# dynalov3.net
KiCad netlist of a schematic drawn in EAGLE
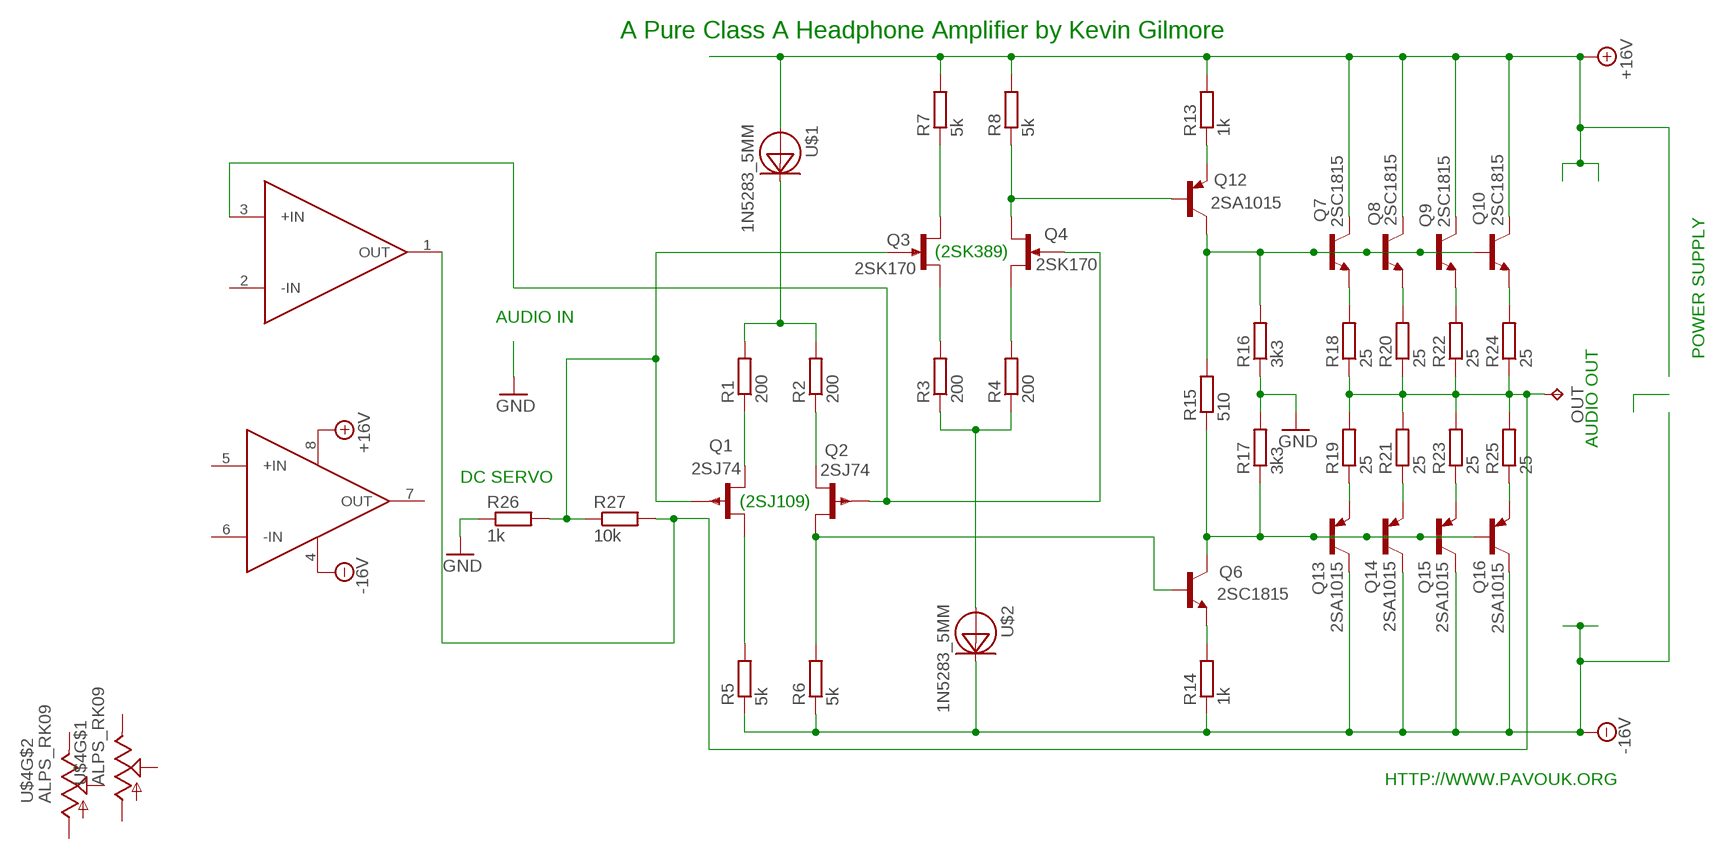
[diagram p0: schematic, sheet 1]

(export (version "E")
  (design (tool "Eeschema 10.0.6"))
  (components
    (comp (ref "OUT")
      (value "TPPAD1-20")
      (footprint "eagle-import:P1-20")
      (libsource (lib "eagle-import") (part "TPPAD1-20"))
    )
    (comp (ref "Q1")
      (value "2SJ74")
      (footprint "eagle-import:TO92F")
      (libsource (lib "eagle-import") (part "2N3820"))
    )
    (comp (ref "Q2")
      (value "2SJ74")
      (footprint "eagle-import:TO92F")
      (libsource (lib "eagle-import") (part "2N3820"))
    )
    (comp (ref "Q3")
      (value "2SK170")
      (footprint "eagle-import:TO92F")
      (libsource (lib "eagle-import") (part "2N3819"))
    )
    (comp (ref "Q4")
      (value "2SK170")
      (footprint "eagle-import:TO92F")
      (libsource (lib "eagle-import") (part "2N3819"))
    )
    (comp (ref "Q6")
      (value "2SC1815")
      (footprint "eagle-import:TO92-ECB")
      (libsource (lib "eagle-import") (part "2SC1815"))
    )
    (comp (ref "Q7")
      (value "2SC1815")
      (footprint "eagle-import:TO92-ECB")
      (libsource (lib "eagle-import") (part "2SC1815"))
    )
    (comp (ref "Q8")
      (value "2SC1815")
      (footprint "eagle-import:TO92-ECB")
      (libsource (lib "eagle-import") (part "2SC1815"))
    )
    (comp (ref "Q9")
      (value "2SC1815")
      (footprint "eagle-import:TO92-ECB")
      (libsource (lib "eagle-import") (part "2SC1815"))
    )
    (comp (ref "Q10")
      (value "2SC1815")
      (footprint "eagle-import:TO92-ECB")
      (libsource (lib "eagle-import") (part "2SC1815"))
    )
    (comp (ref "Q12")
      (value "2SA1015")
      (footprint "eagle-import:TO92-ECB")
      (libsource (lib "eagle-import") (part "-PNP-TO92-ECB"))
    )
    (comp (ref "Q13")
      (value "2SA1015")
      (footprint "eagle-import:TO92-ECB")
      (libsource (lib "eagle-import") (part "-PNP-TO92-ECB"))
    )
    (comp (ref "Q14")
      (value "2SA1015")
      (footprint "eagle-import:TO92-ECB")
      (libsource (lib "eagle-import") (part "-PNP-TO92-ECB"))
    )
    (comp (ref "Q15")
      (value "2SA1015")
      (footprint "eagle-import:TO92-ECB")
      (libsource (lib "eagle-import") (part "-PNP-TO92-ECB"))
    )
    (comp (ref "Q16")
      (value "2SA1015")
      (footprint "eagle-import:TO92-ECB")
      (libsource (lib "eagle-import") (part "-PNP-TO92-ECB"))
    )
    (comp (ref "R1")
      (value "200")
      (footprint "eagle-import:MINI_MELF-0204W")
      (libsource (lib "eagle-import") (part "R-EU_MELF0204W"))
    )
    (comp (ref "R2")
      (value "200")
      (footprint "eagle-import:MINI_MELF-0204W")
      (libsource (lib "eagle-import") (part "R-EU_MELF0204W"))
    )
    (comp (ref "R3")
      (value "200")
      (footprint "eagle-import:MINI_MELF-0204W")
      (libsource (lib "eagle-import") (part "R-EU_MELF0204W"))
    )
    (comp (ref "R4")
      (value "200")
      (footprint "eagle-import:MINI_MELF-0204W")
      (libsource (lib "eagle-import") (part "R-EU_MELF0204W"))
    )
    (comp (ref "R5")
      (value "5k")
      (footprint "eagle-import:MINI_MELF-0204W")
      (libsource (lib "eagle-import") (part "R-EU_MELF0204W"))
    )
    (comp (ref "R6")
      (value "5k")
      (footprint "eagle-import:MINI_MELF-0204W")
      (libsource (lib "eagle-import") (part "R-EU_MELF0204W"))
    )
    (comp (ref "R7")
      (value "5k")
      (footprint "eagle-import:MINI_MELF-0204W")
      (libsource (lib "eagle-import") (part "R-EU_MELF0204W"))
    )
    (comp (ref "R8")
      (value "5k")
      (footprint "eagle-import:MINI_MELF-0204W")
      (libsource (lib "eagle-import") (part "R-EU_MELF0204W"))
    )
    (comp (ref "R13")
      (value "1k")
      (footprint "eagle-import:MINI_MELF-0204W")
      (libsource (lib "eagle-import") (part "R-EU_MELF0204W"))
    )
    (comp (ref "R14")
      (value "1k")
      (footprint "eagle-import:MINI_MELF-0204W")
      (libsource (lib "eagle-import") (part "R-EU_MELF0204W"))
    )
    (comp (ref "R15")
      (value "510")
      (footprint "eagle-import:MINI_MELF-0204W")
      (libsource (lib "eagle-import") (part "R-EU_MELF0204W"))
    )
    (comp (ref "R16")
      (value "3k3")
      (footprint "eagle-import:MINI_MELF-0204W")
      (libsource (lib "eagle-import") (part "R-EU_MELF0204W"))
    )
    (comp (ref "R17")
      (value "3k3")
      (footprint "eagle-import:MINI_MELF-0204W")
      (libsource (lib "eagle-import") (part "R-EU_MELF0204W"))
    )
    (comp (ref "R18")
      (value "25")
      (footprint "eagle-import:MINI_MELF-0204W")
      (libsource (lib "eagle-import") (part "R-EU_MELF0204W"))
    )
    (comp (ref "R19")
      (value "25")
      (footprint "eagle-import:MINI_MELF-0204W")
      (libsource (lib "eagle-import") (part "R-EU_MELF0204W"))
    )
    (comp (ref "R20")
      (value "25")
      (footprint "eagle-import:MINI_MELF-0204W")
      (libsource (lib "eagle-import") (part "R-EU_MELF0204W"))
    )
    (comp (ref "R21")
      (value "25")
      (footprint "eagle-import:MINI_MELF-0204W")
      (libsource (lib "eagle-import") (part "R-EU_MELF0204W"))
    )
    (comp (ref "R22")
      (value "25")
      (footprint "eagle-import:MINI_MELF-0204W")
      (libsource (lib "eagle-import") (part "R-EU_MELF0204W"))
    )
    (comp (ref "R23")
      (value "25")
      (footprint "eagle-import:MINI_MELF-0204W")
      (libsource (lib "eagle-import") (part "R-EU_MELF0204W"))
    )
    (comp (ref "R24")
      (value "25")
      (footprint "eagle-import:MINI_MELF-0204W")
      (libsource (lib "eagle-import") (part "R-EU_MELF0204W"))
    )
    (comp (ref "R25")
      (value "25")
      (footprint "eagle-import:MINI_MELF-0204W")
      (libsource (lib "eagle-import") (part "R-EU_MELF0204W"))
    )
    (comp (ref "R26")
      (value "1k")
      (footprint "eagle-import:MINI_MELF-0204W")
      (libsource (lib "eagle-import") (part "R-EU_MELF0204W"))
    )
    (comp (ref "R27")
      (value "10k")
      (footprint "eagle-import:MINI_MELF-0204W")
      (libsource (lib "eagle-import") (part "R-EU_MELF0204W"))
    )
    (comp (ref "U$1")
      (value "1N5283_5MM")
      (footprint "eagle-import:DO-35-2")
      (libsource (lib "eagle-import") (part "1N5283_5MM"))
    )
    (comp (ref "U$2")
      (value "1N5283_5MM")
      (footprint "eagle-import:DO-35-2")
      (libsource (lib "eagle-import") (part "1N5283_5MM"))
    )
    (comp (ref "U$3")
      (value "LME49720")
      (footprint "eagle-import:DIL08")
      (libsource (lib "eagle-import") (part "LME49720"))
    )
    (comp (ref "U$4")
      (value "ALPS_RK09")
      (footprint "eagle-import:RK09")
      (libsource (lib "eagle-import") (part "ALPS_RK09"))
    )
  )
  (nets
    (net (code "1") (name "+16V") (class "Default")
      (node (ref "Q10") (pin "C") (pinfunction "C_C") (pintype "passive"))
      (node (ref "Q7") (pin "C") (pinfunction "C_C") (pintype "passive"))
      (node (ref "Q8") (pin "C") (pinfunction "C_C") (pintype "passive"))
      (node (ref "Q9") (pin "C") (pinfunction "C_C") (pintype "passive"))
      (node (ref "R13") (pin "2") (pinfunction "2_2") (pintype "passive"))
      (node (ref "R7") (pin "2") (pinfunction "2_2") (pintype "passive"))
      (node (ref "R8") (pin "2") (pinfunction "2_2") (pintype "passive"))
      (node (ref "U$1") (pin "ANODE") (pinfunction "ANODE_ANODE") (pintype "passive"))
      (node (ref "U$3") (pin "8") (pinfunction "V+_8") (pintype "bidirectional"))
    )
    (net (code "2") (name "-16V") (class "Default")
      (node (ref "Q13") (pin "C") (pinfunction "C_C") (pintype "passive"))
      (node (ref "Q14") (pin "C") (pinfunction "C_C") (pintype "passive"))
      (node (ref "Q15") (pin "C") (pinfunction "C_C") (pintype "passive"))
      (node (ref "Q16") (pin "C") (pinfunction "C_C") (pintype "passive"))
      (node (ref "R14") (pin "1") (pinfunction "1_1") (pintype "passive"))
      (node (ref "R5") (pin "1") (pinfunction "1_1") (pintype "passive"))
      (node (ref "R6") (pin "1") (pinfunction "1_1") (pintype "passive"))
      (node (ref "U$2") (pin "CATHODE") (pinfunction "CATHODE_CATHODE") (pintype "passive"))
      (node (ref "U$3") (pin "4") (pinfunction "V-_4") (pintype "bidirectional"))
    )
    (net (code "3") (name "GND") (class "Default")
      (node (ref "R16") (pin "1") (pinfunction "1_1") (pintype "passive"))
      (node (ref "R17") (pin "2") (pinfunction "2_2") (pintype "passive"))
      (node (ref "R26") (pin "1") (pinfunction "1_1") (pintype "passive"))
    )
    (net (code "4") (name "Net-(Q1-PadD)") (class "Default")
      (node (ref "Q1") (pin "D") (pinfunction "D_D") (pintype "passive"))
      (node (ref "R1") (pin "1") (pinfunction "1_1") (pintype "passive"))
    )
    (net (code "5") (name "Net-(Q1-PadG)") (class "Default")
      (node (ref "Q1") (pin "G") (pinfunction "G_G") (pintype "passive"))
      (node (ref "Q3") (pin "G") (pinfunction "G_G") (pintype "passive"))
      (node (ref "R26") (pin "2") (pinfunction "2_2") (pintype "passive"))
      (node (ref "R27") (pin "1") (pinfunction "1_1") (pintype "passive"))
    )
    (net (code "6") (name "Net-(Q1-PadS)") (class "Default")
      (node (ref "Q1") (pin "S") (pinfunction "S_S") (pintype "passive"))
      (node (ref "R5") (pin "2") (pinfunction "2_2") (pintype "passive"))
    )
    (net (code "7") (name "Net-(Q2-PadD)") (class "Default")
      (node (ref "Q2") (pin "D") (pinfunction "D_D") (pintype "passive"))
      (node (ref "Q6") (pin "B") (pinfunction "B_B") (pintype "passive"))
      (node (ref "R6") (pin "2") (pinfunction "2_2") (pintype "passive"))
    )
    (net (code "8") (name "Net-(Q2-PadS)") (class "Default")
      (node (ref "Q2") (pin "S") (pinfunction "S_S") (pintype "passive"))
      (node (ref "R2") (pin "1") (pinfunction "1_1") (pintype "passive"))
    )
    (net (code "9") (name "Net-(Q3-PadD)") (class "Default")
      (node (ref "Q3") (pin "D") (pinfunction "D_D") (pintype "passive"))
      (node (ref "R7") (pin "1") (pinfunction "1_1") (pintype "passive"))
    )
    (net (code "10") (name "Net-(Q3-PadS)") (class "Default")
      (node (ref "Q3") (pin "S") (pinfunction "S_S") (pintype "passive"))
      (node (ref "R3") (pin "2") (pinfunction "2_2") (pintype "passive"))
    )
    (net (code "11") (name "Net-(Q4-PadD)") (class "Default")
      (node (ref "Q4") (pin "D") (pinfunction "D_D") (pintype "passive"))
      (node (ref "R4") (pin "2") (pinfunction "2_2") (pintype "passive"))
    )
    (net (code "12") (name "Net-(Q6-PadE)") (class "Default")
      (node (ref "Q6") (pin "E") (pinfunction "E_E") (pintype "passive"))
      (node (ref "R14") (pin "2") (pinfunction "2_2") (pintype "passive"))
    )
    (net (code "13") (name "Net-(Q7-PadE)") (class "Default")
      (node (ref "Q7") (pin "E") (pinfunction "E_E") (pintype "passive"))
      (node (ref "R18") (pin "2") (pinfunction "2_2") (pintype "passive"))
    )
    (net (code "14") (name "Net-(Q8-PadE)") (class "Default")
      (node (ref "Q8") (pin "E") (pinfunction "E_E") (pintype "passive"))
      (node (ref "R20") (pin "2") (pinfunction "2_2") (pintype "passive"))
    )
    (net (code "15") (name "Net-(Q9-PadE)") (class "Default")
      (node (ref "Q9") (pin "E") (pinfunction "E_E") (pintype "passive"))
      (node (ref "R22") (pin "2") (pinfunction "2_2") (pintype "passive"))
    )
    (net (code "16") (name "Net-(Q10-PadB)") (class "Default")
      (node (ref "Q10") (pin "B") (pinfunction "B_B") (pintype "passive"))
      (node (ref "Q12") (pin "C") (pinfunction "C_C") (pintype "passive"))
      (node (ref "Q7") (pin "B") (pinfunction "B_B") (pintype "passive"))
      (node (ref "Q8") (pin "B") (pinfunction "B_B") (pintype "passive"))
      (node (ref "Q9") (pin "B") (pinfunction "B_B") (pintype "passive"))
      (node (ref "R15") (pin "2") (pinfunction "2_2") (pintype "passive"))
      (node (ref "R16") (pin "2") (pinfunction "2_2") (pintype "passive"))
    )
    (net (code "17") (name "Net-(Q10-PadE)") (class "Default")
      (node (ref "Q10") (pin "E") (pinfunction "E_E") (pintype "passive"))
      (node (ref "R24") (pin "2") (pinfunction "2_2") (pintype "passive"))
    )
    (net (code "18") (name "Net-(Q12-PadB)") (class "Default")
      (node (ref "Q12") (pin "B") (pinfunction "B_B") (pintype "passive"))
      (node (ref "Q4") (pin "S") (pinfunction "S_S") (pintype "passive"))
      (node (ref "R8") (pin "1") (pinfunction "1_1") (pintype "passive"))
    )
    (net (code "19") (name "Net-(Q12-PadE)") (class "Default")
      (node (ref "Q12") (pin "E") (pinfunction "E_E") (pintype "passive"))
      (node (ref "R13") (pin "1") (pinfunction "1_1") (pintype "passive"))
    )
    (net (code "20") (name "Net-(Q13-PadB)") (class "Default")
      (node (ref "Q13") (pin "B") (pinfunction "B_B") (pintype "passive"))
      (node (ref "Q14") (pin "B") (pinfunction "B_B") (pintype "passive"))
      (node (ref "Q15") (pin "B") (pinfunction "B_B") (pintype "passive"))
      (node (ref "Q16") (pin "B") (pinfunction "B_B") (pintype "passive"))
      (node (ref "Q6") (pin "C") (pinfunction "C_C") (pintype "passive"))
      (node (ref "R15") (pin "1") (pinfunction "1_1") (pintype "passive"))
      (node (ref "R17") (pin "1") (pinfunction "1_1") (pintype "passive"))
    )
    (net (code "21") (name "Net-(Q13-PadE)") (class "Default")
      (node (ref "Q13") (pin "E") (pinfunction "E_E") (pintype "passive"))
      (node (ref "R19") (pin "1") (pinfunction "1_1") (pintype "passive"))
    )
    (net (code "22") (name "Net-(Q14-PadE)") (class "Default")
      (node (ref "Q14") (pin "E") (pinfunction "E_E") (pintype "passive"))
      (node (ref "R21") (pin "1") (pinfunction "1_1") (pintype "passive"))
    )
    (net (code "23") (name "Net-(Q15-PadE)") (class "Default")
      (node (ref "Q15") (pin "E") (pinfunction "E_E") (pintype "passive"))
      (node (ref "R23") (pin "1") (pinfunction "1_1") (pintype "passive"))
    )
    (net (code "24") (name "Net-(Q16-PadE)") (class "Default")
      (node (ref "Q16") (pin "E") (pinfunction "E_E") (pintype "passive"))
      (node (ref "R25") (pin "1") (pinfunction "1_1") (pintype "passive"))
    )
    (net (code "25") (name "Net-(R1-Pad2)") (class "Default")
      (node (ref "R1") (pin "2") (pinfunction "2_2") (pintype "passive"))
      (node (ref "R2") (pin "2") (pinfunction "2_2") (pintype "passive"))
      (node (ref "U$1") (pin "CATHODE") (pinfunction "CATHODE_CATHODE") (pintype "passive"))
    )
    (net (code "26") (name "Net-(R3-Pad1)") (class "Default")
      (node (ref "R3") (pin "1") (pinfunction "1_1") (pintype "passive"))
      (node (ref "R4") (pin "1") (pinfunction "1_1") (pintype "passive"))
      (node (ref "U$2") (pin "ANODE") (pinfunction "ANODE_ANODE") (pintype "passive"))
    )
    (net (code "27") (name "Net-(U$3A-+IN)") (class "Default")
      (node (ref "Q2") (pin "G") (pinfunction "G_G") (pintype "passive"))
      (node (ref "Q4") (pin "G") (pinfunction "G_G") (pintype "passive"))
      (node (ref "U$3") (pin "3") (pinfunction "+IN_3") (pintype "bidirectional"))
    )
    (net (code "28") (name "Net-(U$3A-OUT)") (class "Default")
      (node (ref "OUT") (pin "TP") (pinfunction "TP_TP") (pintype "input"))
      (node (ref "R18") (pin "1") (pinfunction "1_1") (pintype "passive"))
      (node (ref "R19") (pin "2") (pinfunction "2_2") (pintype "passive"))
      (node (ref "R20") (pin "1") (pinfunction "1_1") (pintype "passive"))
      (node (ref "R21") (pin "2") (pinfunction "2_2") (pintype "passive"))
      (node (ref "R22") (pin "1") (pinfunction "1_1") (pintype "passive"))
      (node (ref "R23") (pin "2") (pinfunction "2_2") (pintype "passive"))
      (node (ref "R24") (pin "1") (pinfunction "1_1") (pintype "passive"))
      (node (ref "R25") (pin "2") (pinfunction "2_2") (pintype "passive"))
      (node (ref "R27") (pin "2") (pinfunction "2_2") (pintype "passive"))
      (node (ref "U$3") (pin "1") (pinfunction "OUT_1") (pintype "bidirectional"))
    )
    (net (code "29") (name "unconnected-(U$3A--IN-Pad2)") (class "Default")
      (node (ref "U$3") (pin "2") (pinfunction "-IN_2") (pintype "bidirectional"))
    )
    (net (code "30") (name "unconnected-(U$3B-+IN-Pad5)") (class "Default")
      (node (ref "U$3") (pin "5") (pinfunction "+IN_5") (pintype "bidirectional"))
    )
    (net (code "31") (name "unconnected-(U$3B--IN-Pad6)") (class "Default")
      (node (ref "U$3") (pin "6") (pinfunction "-IN_6") (pintype "bidirectional"))
    )
    (net (code "32") (name "unconnected-(U$3B-OUT-Pad7)") (class "Default")
      (node (ref "U$3") (pin "7") (pinfunction "OUT_7") (pintype "bidirectional"))
    )
    (net (code "33") (name "unconnected-(U$4A-1-PadG1)") (class "Default")
      (node (ref "U$4") (pin "G1") (pinfunction "1_G1") (pintype "passive"))
    )
    (net (code "34") (name "unconnected-(U$4A-2-PadO1)") (class "Default")
      (node (ref "U$4") (pin "O1") (pinfunction "2_O1") (pintype "passive"))
    )
    (net (code "35") (name "unconnected-(U$4A-3-PadI1)") (class "Default")
      (node (ref "U$4") (pin "I1") (pinfunction "3_I1") (pintype "passive"))
    )
    (net (code "36") (name "unconnected-(U$4B-1-PadG2)") (class "Default")
      (node (ref "U$4") (pin "G2") (pinfunction "1_G2") (pintype "passive"))
    )
    (net (code "37") (name "unconnected-(U$4B-2-PadO2)") (class "Default")
      (node (ref "U$4") (pin "O2") (pinfunction "2_O2") (pintype "passive"))
    )
    (net (code "38") (name "unconnected-(U$4B-3-PadI2)") (class "Default")
      (node (ref "U$4") (pin "I2") (pinfunction "3_I2") (pintype "passive"))
    )
  )
)
